# DM2080_EEPROM.net
KiCad netlist of a schematic drawn in Altium Designer
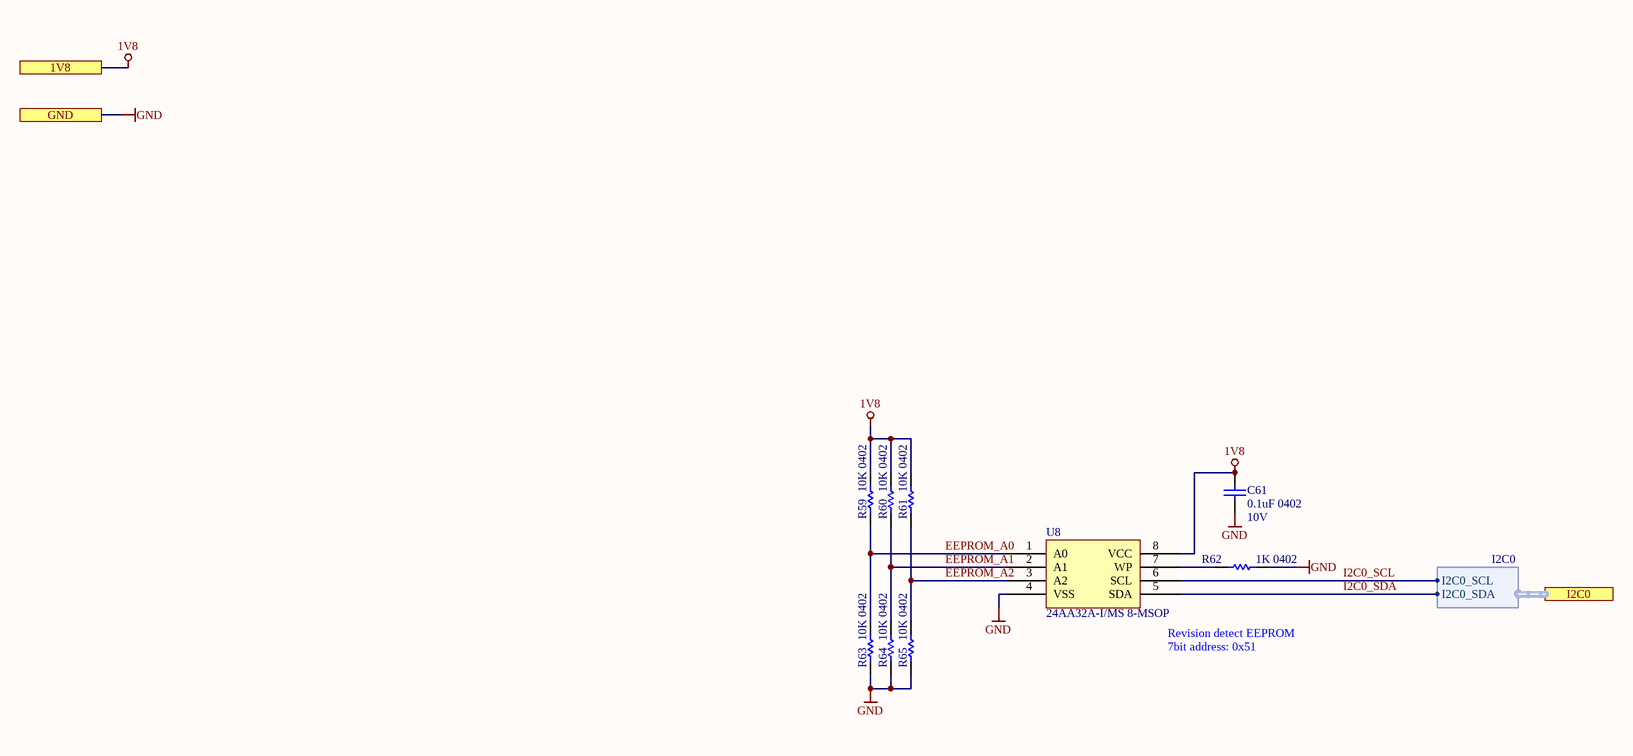
[diagram p0: DM2080_EEPROM.SchDoc]

(export (version "E")
  (design (tool "Eeschema 10.0.6"))
  (components
    (comp (ref "C61")
      (value "0.1uF 0402")
      (footprint "CAP_Altium_Vault_Generic:CAPC0402(1005)70_L")
      (description "CAP CER 0.1UF 10V X7R 0402 5%")
      (fields (field (name "TOLERANCE") "5%") (field (name "VOLTAGE RATING") "10V"))
      (libsource (lib "LuxonisMaster") (part "GRM155R71A104JA01D"))
    )
    (comp (ref "R59")
      (value "10K 0402")
      (footprint "RES_Altium_Vault_Generic:RESC0402(1005)_L")
      (fields (field (name "TOLERANCE") "1%"))
      (libsource (lib "LuxonisMaster") (part "RC0402FR-1310KL"))
    )
    (comp (ref "R60")
      (value "10K 0402")
      (footprint "RES_Altium_Vault_Generic:RESC0402(1005)_L")
      (fields (field (name "TOLERANCE") "1%"))
      (libsource (lib "LuxonisMaster") (part "RC0402FR-1310KL"))
    )
    (comp (ref "R61")
      (value "10K 0402")
      (footprint "RES_Altium_Vault_Generic:RESC0402(1005)_L")
      (fields (field (name "TOLERANCE") "1%"))
      (libsource (lib "LuxonisMaster") (part "RC0402FR-1310KL"))
    )
    (comp (ref "R62")
      (value "1K 0402")
      (footprint "RES_Altium_Vault_Generic:RESC0402(1005)_L")
      (description "RES SMD 1K OHM 1% 1/16W 0402")
      (fields (field (name "TOLERANCE") "1%"))
      (libsource (lib "LuxonisMaster") (part "RC0402FR-071KL"))
    )
    (comp (ref "R63")
      (value "10K 0402")
      (footprint "RES_Altium_Vault_Generic:RESC0402(1005)_L")
      (fields (field (name "TOLERANCE") "1%"))
      (libsource (lib "LuxonisMaster") (part "RC0402FR-1310KL"))
    )
    (comp (ref "R64")
      (value "10K 0402")
      (footprint "RES_Altium_Vault_Generic:RESC0402(1005)_L")
      (fields (field (name "TOLERANCE") "1%"))
      (libsource (lib "LuxonisMaster") (part "RC0402FR-1310KL"))
    )
    (comp (ref "R65")
      (value "10K 0402")
      (footprint "RES_Altium_Vault_Generic:RESC0402(1005)_L")
      (fields (field (name "TOLERANCE") "1%"))
      (libsource (lib "LuxonisMaster") (part "RC0402FR-1310KL"))
    )
    (comp (ref "U8")
      (value "24AA32A-I/MS 8-MSOP")
      (footprint "LuxonisMaster:24AA32A-I/MS")
      (description "IC EEPROM 32K I2C 400KHZ 8MSOP Memory IC 32Kb (4K x 8) I²C 400kHz 900ns 8-MSOP")
      (libsource (lib "LuxonisMaster") (part "24AA32A-I/MS"))
    )
  )
  (nets
    (net (code "2") (name "/EEPROM_A0") (class "Default")
      (node (ref "R59") (pin "1") (pinfunction "1_1") (pintype "passive"))
      (node (ref "R63") (pin "2") (pinfunction "2_2") (pintype "passive"))
      (node (ref "U8") (pin "1") (pinfunction "A0_1") (pintype "passive"))
    )
    (net (code "3") (name "/EEPROM_A1") (class "Default")
      (node (ref "R60") (pin "1") (pinfunction "1_1") (pintype "passive"))
      (node (ref "R64") (pin "2") (pinfunction "2_2") (pintype "passive"))
      (node (ref "U8") (pin "2") (pinfunction "A1_2") (pintype "passive"))
    )
    (net (code "4") (name "/EEPROM_A2") (class "Default")
      (node (ref "R61") (pin "1") (pinfunction "1_1") (pintype "passive"))
      (node (ref "R65") (pin "2") (pinfunction "2_2") (pintype "passive"))
      (node (ref "U8") (pin "3") (pinfunction "A2_3") (pintype "passive"))
    )
    (net (code "5") (name "/I2C0_SCL") (class "Default")
      (node (ref "U8") (pin "6") (pinfunction "SCL_6") (pintype "passive"))
    )
    (net (code "6") (name "/I2C0_SDA") (class "Default")
      (node (ref "U8") (pin "5") (pinfunction "SDA_5") (pintype "passive"))
    )
    (net (code "8") (name "1V8") (class "Default")
      (node (ref "C61") (pin "2") (pinfunction "2_2") (pintype "passive"))
      (node (ref "R59") (pin "2") (pinfunction "2_2") (pintype "passive"))
      (node (ref "R60") (pin "2") (pinfunction "2_2") (pintype "passive"))
      (node (ref "R61") (pin "2") (pinfunction "2_2") (pintype "passive"))
      (node (ref "U8") (pin "8") (pinfunction "VCC_8") (pintype "passive"))
    )
    (net (code "9") (name "GND") (class "Default")
      (node (ref "C61") (pin "1") (pinfunction "1_1") (pintype "passive"))
      (node (ref "R62") (pin "1") (pinfunction "1_1") (pintype "passive"))
      (node (ref "R63") (pin "1") (pinfunction "1_1") (pintype "passive"))
      (node (ref "R64") (pin "1") (pinfunction "1_1") (pintype "passive"))
      (node (ref "R65") (pin "1") (pinfunction "1_1") (pintype "passive"))
      (node (ref "U8") (pin "4") (pinfunction "VSS_4") (pintype "passive"))
    )
    (net (code "10") (name "Net-(U8-WP)") (class "Default")
      (node (ref "R62") (pin "2") (pinfunction "2_2") (pintype "passive"))
      (node (ref "U8") (pin "7") (pinfunction "WP_7") (pintype "passive"))
    )
  )
)
